# 03_MCU.net
KiCad netlist of a schematic drawn in Altium Designer
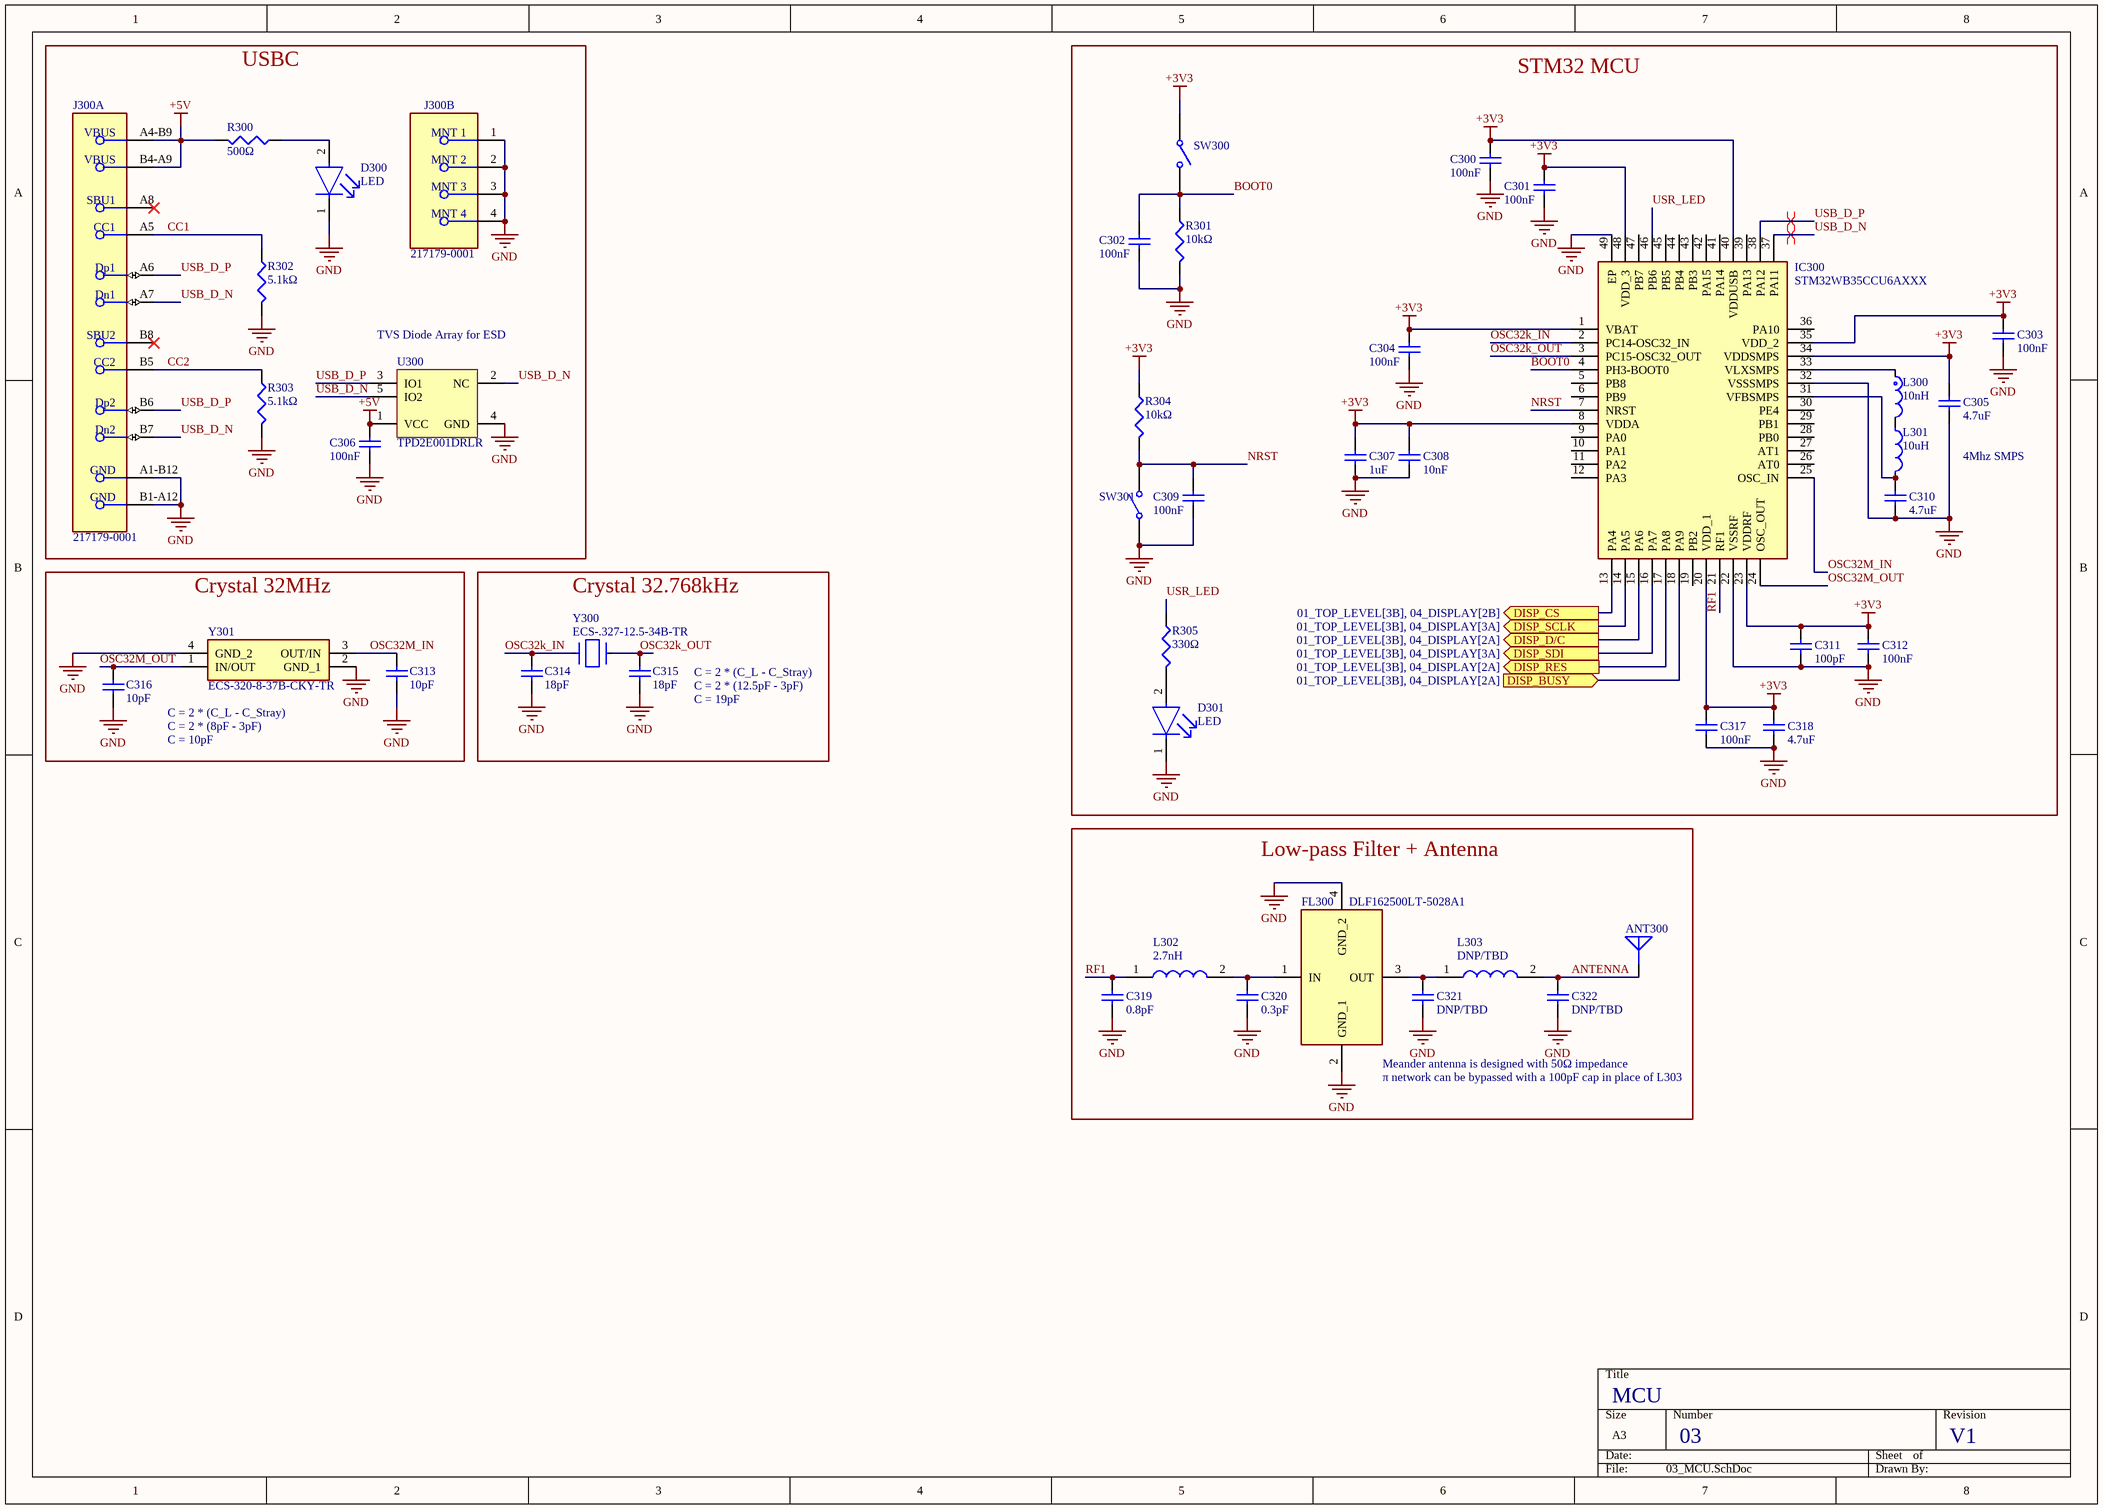
[diagram p0: 03_MCU.SchDoc]

(export (version "E")
  (design (tool "Eeschema 10.0.6"))
  (components
    (comp (ref "ANT300")
      (value "MEANDER_ANTENNA")
      (footprint "MEANDER_ANTENNA")
      (description "2.4GHz meander antenna")
      (libsource (lib "Schlib1") (part "MEANDER_ANTENNA"))
    )
    (comp (ref "C300")
      (value "100nF")
      (footprint "CAPC1005X55X25LL05T10")
      (description "Chip Capacitor, 1 uF, +/- 10%, 6.3 V, 0402 (1005 Metric)")
      (fields (field (name "TOLERANCE") "10%") (field (name "Comment") "Capacitor 1 uF +/- 10% 6.3 V 0402"))
      (libsource (lib "CPRT Workspace") (part "CAP-NP-2"))
    )
    (comp (ref "C301")
      (value "100nF")
      (footprint "CAPC1005X55X25LL05T10")
      (description "Chip Capacitor, 1 uF, +/- 10%, 6.3 V, 0402 (1005 Metric)")
      (fields (field (name "TOLERANCE") "10%") (field (name "Comment") "Capacitor 1 uF +/- 10% 6.3 V 0402"))
      (libsource (lib "CPRT Workspace") (part "CAP-NP-2"))
    )
    (comp (ref "C302")
      (value "100nF")
      (footprint "CAPC1005X55X25LL05T10")
      (description "Chip Capacitor, 1 uF, +/- 10%, 6.3 V, 0402 (1005 Metric)")
      (fields (field (name "TOLERANCE") "10%") (field (name "Comment") "Capacitor 1 uF +/- 10% 6.3 V 0402"))
      (libsource (lib "CPRT Workspace") (part "CAP-NP-2"))
    )
    (comp (ref "C303")
      (value "100nF")
      (footprint "CAPC1005X55X25LL05T10")
      (description "Chip Capacitor, 1 uF, +/- 10%, 6.3 V, 0402 (1005 Metric)")
      (fields (field (name "TOLERANCE") "10%") (field (name "Comment") "Capacitor 1 uF +/- 10% 6.3 V 0402"))
      (libsource (lib "CPRT Workspace") (part "CAP-NP-2"))
    )
    (comp (ref "C304")
      (value "100nF")
      (footprint "CAPC1005X55X25LL05T10")
      (description "Chip Capacitor, 1 uF, +/- 10%, 6.3 V, 0402 (1005 Metric)")
      (fields (field (name "TOLERANCE") "10%") (field (name "Comment") "Capacitor 1 uF +/- 10% 6.3 V 0402"))
      (libsource (lib "CPRT Workspace") (part "CAP-NP-2"))
    )
    (comp (ref "C305")
      (value "4.7uF")
      (footprint "CAPC1005X55X25LL05T10")
      (description "Chip Capacitor, 1 uF, +/- 10%, 6.3 V, 0402 (1005 Metric)")
      (fields (field (name "TOLERANCE") "10%") (field (name "Comment") "Capacitor 1 uF +/- 10% 6.3 V 0402"))
      (libsource (lib "CPRT Workspace") (part "CAP-NP-2"))
    )
    (comp (ref "C306")
      (value "100nF")
      (footprint "CAPC1005X55X25LL05T10")
      (description "Chip Capacitor, 1 uF, +/- 10%, 6.3 V, 0402 (1005 Metric)")
      (fields (field (name "TOLERANCE") "10%") (field (name "Comment") "Capacitor 1 uF +/- 10% 6.3 V 0402"))
      (libsource (lib "CPRT Workspace") (part "CAP-NP-2"))
    )
    (comp (ref "C307")
      (value "1uF")
      (footprint "CAPC1005X55X25LL05T10")
      (description "Chip Capacitor, 1 uF, +/- 10%, 6.3 V, 0402 (1005 Metric)")
      (fields (field (name "TOLERANCE") "10%") (field (name "Comment") "Capacitor 1 uF +/- 10% 6.3 V 0402"))
      (libsource (lib "CPRT Workspace") (part "CAP-NP-2"))
    )
    (comp (ref "C308")
      (value "10nF")
      (footprint "CAPC1005X55X25LL05T10")
      (description "Chip Capacitor, 1 uF, +/- 10%, 6.3 V, 0402 (1005 Metric)")
      (fields (field (name "TOLERANCE") "10%") (field (name "Comment") "Capacitor 1 uF +/- 10% 6.3 V 0402"))
      (libsource (lib "CPRT Workspace") (part "CAP-NP-2"))
    )
    (comp (ref "C309")
      (value "100nF")
      (footprint "CAPC1005X55X25LL05T10")
      (description "Chip Capacitor, 1 uF, +/- 10%, 6.3 V, 0402 (1005 Metric)")
      (fields (field (name "TOLERANCE") "10%") (field (name "Comment") "Capacitor 1 uF +/- 10% 6.3 V 0402"))
      (libsource (lib "CPRT Workspace") (part "CAP-NP-2"))
    )
    (comp (ref "C310")
      (value "4.7uF")
      (footprint "CAPC1005X55X25LL05T10")
      (description "Chip Capacitor, 1 uF, +/- 10%, 6.3 V, 0402 (1005 Metric)")
      (fields (field (name "TOLERANCE") "10%") (field (name "Comment") "Capacitor 1 uF +/- 10% 6.3 V 0402"))
      (libsource (lib "CPRT Workspace") (part "CAP-NP-2"))
    )
    (comp (ref "C311")
      (value "100pF")
      (footprint "CAPC1005X55X25LL05T10")
      (description "Chip Capacitor, 1 uF, +/- 10%, 6.3 V, 0402 (1005 Metric)")
      (fields (field (name "TOLERANCE") "10%") (field (name "Comment") "Capacitor 1 uF +/- 10% 6.3 V 0402"))
      (libsource (lib "CPRT Workspace") (part "CAP-NP-2"))
    )
    (comp (ref "C312")
      (value "100nF")
      (footprint "CAPC1005X55X25LL05T10")
      (description "Chip Capacitor, 1 uF, +/- 10%, 6.3 V, 0402 (1005 Metric)")
      (fields (field (name "TOLERANCE") "10%") (field (name "Comment") "Capacitor 1 uF +/- 10% 6.3 V 0402"))
      (libsource (lib "CPRT Workspace") (part "CAP-NP-2"))
    )
    (comp (ref "C313")
      (value "10pF")
      (footprint "CAPC1005X55X25LL05T10")
      (description "Chip Capacitor, 1 uF, +/- 10%, 6.3 V, 0402 (1005 Metric)")
      (fields (field (name "TOLERANCE") "10%") (field (name "Comment") "Capacitor 1 uF +/- 10% 6.3 V 0402"))
      (libsource (lib "CPRT Workspace") (part "CAP-NP-2"))
    )
    (comp (ref "C314")
      (value "18pF")
      (footprint "CAPC1005X55X25LL05T10")
      (description "Chip Capacitor, 1 uF, +/- 10%, 6.3 V, 0402 (1005 Metric)")
      (fields (field (name "TOLERANCE") "10%") (field (name "Comment") "Capacitor 1 uF +/- 10% 6.3 V 0402"))
      (libsource (lib "CPRT Workspace") (part "CAP-NP-2"))
    )
    (comp (ref "C315")
      (value "18pF")
      (footprint "CAPC1005X55X25LL05T10")
      (description "Chip Capacitor, 1 uF, +/- 10%, 6.3 V, 0402 (1005 Metric)")
      (fields (field (name "TOLERANCE") "10%") (field (name "Comment") "Capacitor 1 uF +/- 10% 6.3 V 0402"))
      (libsource (lib "CPRT Workspace") (part "CAP-NP-2"))
    )
    (comp (ref "C316")
      (value "10pF")
      (footprint "CAPC1005X55X25LL05T10")
      (description "Chip Capacitor, 1 uF, +/- 10%, 6.3 V, 0402 (1005 Metric)")
      (fields (field (name "TOLERANCE") "10%") (field (name "Comment") "Capacitor 1 uF +/- 10% 6.3 V 0402"))
      (libsource (lib "CPRT Workspace") (part "CAP-NP-2"))
    )
    (comp (ref "C317")
      (value "100nF")
      (footprint "CAPC1005X55X25LL05T10")
      (description "Chip Capacitor, 1 uF, +/- 10%, 6.3 V, 0402 (1005 Metric)")
      (fields (field (name "TOLERANCE") "10%") (field (name "Comment") "Capacitor 1 uF +/- 10% 6.3 V 0402"))
      (libsource (lib "CPRT Workspace") (part "CAP-NP-2"))
    )
    (comp (ref "C318")
      (value "4.7uF")
      (footprint "CAPC1005X55X25LL05T10")
      (description "Chip Capacitor, 1 uF, +/- 10%, 6.3 V, 0402 (1005 Metric)")
      (fields (field (name "TOLERANCE") "10%") (field (name "Comment") "Capacitor 1 uF +/- 10% 6.3 V 0402"))
      (libsource (lib "CPRT Workspace") (part "CAP-NP-2"))
    )
    (comp (ref "C319")
      (value "0.8pF")
      (footprint "CAPC1005X55X25LL05T10")
      (description "Chip Capacitor, 1 uF, +/- 10%, 6.3 V, 0402 (1005 Metric)")
      (fields (field (name "TOLERANCE") "10%") (field (name "Comment") "Capacitor 1 uF +/- 10% 6.3 V 0402"))
      (libsource (lib "CPRT Workspace") (part "CAP-NP-2"))
    )
    (comp (ref "C320")
      (value "0.3pF")
      (footprint "CAPC1005X55X25LL05T10")
      (description "Chip Capacitor, 1 uF, +/- 10%, 6.3 V, 0402 (1005 Metric)")
      (fields (field (name "TOLERANCE") "10%") (field (name "Comment") "Capacitor 1 uF +/- 10% 6.3 V 0402"))
      (libsource (lib "CPRT Workspace") (part "CAP-NP-2"))
    )
    (comp (ref "C321")
      (value "DNP/TBD")
      (footprint "CAPC1005X55X25LL05T10")
      (description "Chip Capacitor, 1 uF, +/- 10%, 6.3 V, 0402 (1005 Metric)")
      (fields (field (name "TOLERANCE") "10%") (field (name "Comment") "Capacitor 1 uF +/- 10% 6.3 V 0402"))
      (libsource (lib "CPRT Workspace") (part "CAP-NP-2"))
    )
    (comp (ref "C322")
      (value "DNP/TBD")
      (footprint "CAPC1005X55X25LL05T10")
      (description "Chip Capacitor, 1 uF, +/- 10%, 6.3 V, 0402 (1005 Metric)")
      (fields (field (name "TOLERANCE") "10%") (field (name "Comment") "Capacitor 1 uF +/- 10% 6.3 V 0402"))
      (libsource (lib "CPRT Workspace") (part "CAP-NP-2"))
    )
    (comp (ref "D300")
      (value "LED")
      (footprint "FP-VLMO1500-GS08-MFG")
      (description "VLMO1500-GS08 LED Uni-Color Soft Orange 611nm 2-Pin Chip 0402(1006Metric) T/R")
      (libsource (lib "Altium Content Vault") (part "75a0115997dd6a71327e26aab64f6f8"))
    )
    (comp (ref "D301")
      (value "LED")
      (footprint "FP-VLMO1500-GS08-MFG")
      (description "VLMO1500-GS08 LED Uni-Color Soft Orange 611nm 2-Pin Chip 0402(1006Metric) T/R")
      (libsource (lib "Altium Content Vault") (part "75a0115997dd6a71327e26aab64f6f8"))
    )
    (comp (ref "FL300")
      (value "DLF162500LT-5028A1")
      (footprint "DLF162500LT5028A1")
      (description "Filter")
      (fields (field (name "MOUSER PART NUMBER") "810-DLF16250LT5028A1"))
      (libsource (lib "Schlib1") (part "DLF162500LT-5028A1"))
    )
    (comp (ref "IC300")
      (value "STM32WB35CCU6AXXX")
      (footprint "QFN50P700X700X65-49N-D")
      (description "Integrated Circuit")
      (libsource (lib "Schlib1") (part "STM32WB35CCU6AXXX"))
    )
    (comp (ref "J300")
      (value "217179-0001")
      (footprint "FP-2171790001-MFG")
      (description "CONN RCP USB2.0 TYP C 24P SMD RA")
      (libsource (lib "Altium Content Vault") (part "8b86497a633d14b3f74642136fc0ce6"))
    )
    (comp (ref "L300")
      (value "10nH")
      (footprint "FP-LQG15WH_02-MFG")
      (description "Multilayer type Inductor for Automotive 10nH ±5% 0.19Ω 500mA 0402")
      (fields (field (name "TOLERANCE") "5%"))
      (libsource (lib "Altium Content Vault") (part "4cc4b267dca4c8e51f7102f422741d8"))
    )
    (comp (ref "L301")
      (value "10uH")
      (footprint "FP-LQM21FN_70-MFG")
      (description "FIXED IND 10UH 100MA 780MOHM SMD")
      (fields (field (name "TOLERANCE") "20%"))
      (libsource (lib "Altium Content Vault") (part "725321dda6339637d4d059423bc1c3c"))
    )
    (comp (ref "L302")
      (value "2.7nH")
      (footprint "LQG15WH0N7B02D")
      (description "Inductor")
      (fields
        (field (name "MANUFACTURER_PART_NUMBER") "LQG15HS2N7S02D")
        (field (name "MOUSER PART NUMBER") "81-LQG15HS2N7S02D")
      )
      (libsource (lib "Schlib1") (part "LQG15HS2N7S02D"))
    )
    (comp (ref "L303")
      (value "DNP/TBD")
      (footprint "LQG15WH0N7B02D")
      (description "Inductor")
      (fields
        (field (name "MANUFACTURER_PART_NUMBER") "LQG15HS2N7S02D")
        (field (name "MOUSER PART NUMBER") "81-LQG15HS2N7S02D")
      )
      (libsource (lib "Schlib1") (part "LQG15HS2N7S02D"))
    )
    (comp (ref "R300")
      (value "500Ω")
      (footprint "RESC0402(1005)_L")
      (description "100R 0.063W 1% 0402 (1005 Metric)  SMD")
      (fields (field (name "TOLERANCE") "1%") (field (name "POWER") "63mW"))
      (libsource (lib "CPRT Workspace") (part "100R2F"))
    )
    (comp (ref "R301")
      (value "10kΩ")
      (footprint "RESC0402(1005)_L")
      (description "100R 0.063W 1% 0402 (1005 Metric)  SMD")
      (fields (field (name "TOLERANCE") "1%") (field (name "POWER") "63mW"))
      (libsource (lib "CPRT Workspace") (part "100R2F"))
    )
    (comp (ref "R302")
      (value "5.1kΩ")
      (footprint "RESC0402(1005)_L")
      (description "100R 0.063W 1% 0402 (1005 Metric)  SMD")
      (fields (field (name "TOLERANCE") "1%") (field (name "POWER") "63mW"))
      (libsource (lib "CPRT Workspace") (part "100R2F"))
    )
    (comp (ref "R303")
      (value "5.1kΩ")
      (footprint "RESC0402(1005)_L")
      (description "100R 0.063W 1% 0402 (1005 Metric)  SMD")
      (fields (field (name "TOLERANCE") "1%") (field (name "POWER") "63mW"))
      (libsource (lib "CPRT Workspace") (part "100R2F"))
    )
    (comp (ref "R304")
      (value "10kΩ")
      (footprint "RESC0402(1005)_L")
      (description "100R 0.063W 1% 0402 (1005 Metric)  SMD")
      (fields (field (name "TOLERANCE") "1%") (field (name "POWER") "63mW"))
      (libsource (lib "CPRT Workspace") (part "100R2F"))
    )
    (comp (ref "R305")
      (value "330Ω")
      (footprint "RESC0402(1005)_L")
      (description "100R 0.063W 1% 0402 (1005 Metric)  SMD")
      (fields (field (name "TOLERANCE") "1%") (field (name "POWER") "63mW"))
      (libsource (lib "CPRT Workspace") (part "100R2F"))
    )
    (comp (ref "SW300")
      (value "434111050826")
      (footprint "434111050826")
      (description "Switch Tactile Spst-no 0.05A 12V")
      (libsource (lib "Altium Content Vault") (part "SPST-NO_2P"))
    )
    (comp (ref "SW301")
      (value "434111050826")
      (footprint "434111050826")
      (description "Switch Tactile Spst-no 0.05A 12V")
      (libsource (lib "Altium Content Vault") (part "SPST-NO_2P"))
    )
    (comp (ref "U300")
      (value "TPD2E001DRLR")
      (footprint "DRL0005A_L")
      (fields (field (name "MANUFACTURER") "Texas Instruments"))
      (libsource (lib "Altium Content Vault") (part "TI-TPD2E001-SOT_DRL-5"))
    )
    (comp (ref "Y300")
      (value "ECS-.327-12.5-34B-TR")
      (footprint "FP-ECX-31B-MFG")
      (description "CRYSTAL 32.7680KHZ 12.5PF SMD")
      (libsource (lib "Altium Content Vault") (part "99724985039315a44fd0d1401b84e49"))
    )
    (comp (ref "Y301")
      (value "ECS-320-8-37B-CKY-TR")
      (footprint "ECS320837BCKYTR")
      (description "Crystal or Oscillator")
      (fields (field (name "MOUSER PART NUMBER") "520-320-8-37B-CKYT"))
      (libsource (lib "Schlib1") (part "ECS-320-8-37B-CKY-TR"))
    )
  )
  (nets
    (net (code "1") (name "+3V3") (class "Default")
      (node (ref "C300") (pin "2") (pinfunction "2_2") (pintype "passive"))
      (node (ref "C301") (pin "2") (pinfunction "2_2") (pintype "passive"))
      (node (ref "C303") (pin "2") (pinfunction "2_2") (pintype "passive"))
      (node (ref "C304") (pin "2") (pinfunction "2_2") (pintype "passive"))
      (node (ref "C305") (pin "2") (pinfunction "2_2") (pintype "passive"))
      (node (ref "C307") (pin "2") (pinfunction "2_2") (pintype "passive"))
      (node (ref "C308") (pin "2") (pinfunction "2_2") (pintype "passive"))
      (node (ref "C311") (pin "2") (pinfunction "2_2") (pintype "passive"))
      (node (ref "C312") (pin "2") (pinfunction "2_2") (pintype "passive"))
      (node (ref "C317") (pin "2") (pinfunction "2_2") (pintype "passive"))
      (node (ref "C318") (pin "2") (pinfunction "2_2") (pintype "passive"))
      (node (ref "IC300") (pin "1") (pinfunction "VBAT_1") (pintype "passive"))
      (node (ref "IC300") (pin "20") (pinfunction "VDD_1_20") (pintype "passive"))
      (node (ref "IC300") (pin "23") (pinfunction "VDDRF_23") (pintype "passive"))
      (node (ref "IC300") (pin "34") (pinfunction "VDDSMPS_34") (pintype "passive"))
      (node (ref "IC300") (pin "35") (pinfunction "VDD_2_35") (pintype "passive"))
      (node (ref "IC300") (pin "40") (pinfunction "VDDUSB_40") (pintype "passive"))
      (node (ref "IC300") (pin "48") (pinfunction "VDD_3_48") (pintype "passive"))
      (node (ref "IC300") (pin "8") (pinfunction "VDDA_8") (pintype "passive"))
      (node (ref "R304") (pin "1") (pinfunction "1_1") (pintype "passive"))
      (node (ref "SW300") (pin "1") (pinfunction "1_1") (pintype "passive"))
    )
    (net (code "2") (name "+5V") (class "Default")
      (node (ref "C306") (pin "2") (pinfunction "2_2") (pintype "passive"))
      (node (ref "J300") (pin "A4-B9") (pinfunction "VBUS_A4-B9") (pintype "power_in"))
      (node (ref "J300") (pin "B4-A9") (pinfunction "VBUS_B4-A9") (pintype "power_in"))
      (node (ref "R300") (pin "2") (pinfunction "2_2") (pintype "passive"))
      (node (ref "U300") (pin "1") (pinfunction "VCC_1") (pintype "power_in"))
    )
    (net (code "3") (name "/ANTENNA") (class "Default")
      (node (ref "ANT300") (pin "0") (pinfunction "0_0") (pintype "passive"))
      (node (ref "C322") (pin "2") (pinfunction "2_2") (pintype "passive"))
      (node (ref "L303") (pin "2") (pinfunction "2_2") (pintype "passive"))
    )
    (net (code "4") (name "/BOOT0") (class "Default")
      (node (ref "C302") (pin "2") (pinfunction "2_2") (pintype "passive"))
      (node (ref "IC300") (pin "4") (pinfunction "PH3-BOOT0_4") (pintype "passive"))
      (node (ref "R301") (pin "1") (pinfunction "1_1") (pintype "passive"))
      (node (ref "SW300") (pin "2") (pinfunction "2_2") (pintype "passive"))
    )
    (net (code "5") (name "/CC1") (class "Default")
      (node (ref "J300") (pin "A5") (pinfunction "CC1_A5") (pintype "passive"))
      (node (ref "R302") (pin "1") (pinfunction "1_1") (pintype "passive"))
    )
    (net (code "6") (name "/CC2") (class "Default")
      (node (ref "J300") (pin "B5") (pinfunction "CC2_B5") (pintype "passive"))
      (node (ref "R303") (pin "1") (pinfunction "1_1") (pintype "passive"))
    )
    (net (code "7") (name "/DISP_BUSY") (class "Default")
      (node (ref "IC300") (pin "18") (pinfunction "PA9_18") (pintype "passive"))
    )
    (net (code "8") (name "/DISP_CS") (class "Default")
      (node (ref "IC300") (pin "13") (pinfunction "PA4_13") (pintype "passive"))
    )
    (net (code "9") (name "/DISP_D{slash}C") (class "Default")
      (node (ref "IC300") (pin "15") (pinfunction "PA6_15") (pintype "passive"))
    )
    (net (code "10") (name "/DISP_RES") (class "Default")
      (node (ref "IC300") (pin "17") (pinfunction "PA8_17") (pintype "passive"))
    )
    (net (code "11") (name "/DISP_SCLK") (class "Default")
      (node (ref "IC300") (pin "14") (pinfunction "PA5_14") (pintype "passive"))
    )
    (net (code "12") (name "/DISP_SDI") (class "Default")
      (node (ref "IC300") (pin "16") (pinfunction "PA7_16") (pintype "passive"))
    )
    (net (code "13") (name "/NRST") (class "Default")
      (node (ref "C309") (pin "2") (pinfunction "2_2") (pintype "passive"))
      (node (ref "IC300") (pin "7") (pinfunction "NRST_7") (pintype "passive"))
      (node (ref "R304") (pin "2") (pinfunction "2_2") (pintype "passive"))
      (node (ref "SW301") (pin "2") (pinfunction "2_2") (pintype "passive"))
    )
    (net (code "14") (name "/OSC32M_IN") (class "Default")
      (node (ref "C313") (pin "2") (pinfunction "2_2") (pintype "passive"))
      (node (ref "IC300") (pin "25") (pinfunction "OSC_IN_25") (pintype "passive"))
      (node (ref "Y301") (pin "3") (pinfunction "OUT/IN_3") (pintype "passive"))
    )
    (net (code "15") (name "/OSC32M_OUT") (class "Default")
      (node (ref "C316") (pin "2") (pinfunction "2_2") (pintype "passive"))
      (node (ref "IC300") (pin "24") (pinfunction "OSC_OUT_24") (pintype "passive"))
      (node (ref "Y301") (pin "1") (pinfunction "IN/OUT_1") (pintype "passive"))
    )
    (net (code "16") (name "/OSC32k_IN") (class "Default")
      (node (ref "C314") (pin "2") (pinfunction "2_2") (pintype "passive"))
      (node (ref "IC300") (pin "2") (pinfunction "PC14-OSC32_IN_2") (pintype "passive"))
      (node (ref "Y300") (pin "1") (pinfunction "In/Out_1") (pintype "passive"))
    )
    (net (code "17") (name "/OSC32k_OUT") (class "Default")
      (node (ref "C315") (pin "2") (pinfunction "2_2") (pintype "passive"))
      (node (ref "IC300") (pin "3") (pinfunction "PC15-OSC32_OUT_3") (pintype "passive"))
      (node (ref "Y300") (pin "2") (pinfunction "Out/In_2") (pintype "passive"))
    )
    (net (code "18") (name "/RF1") (class "Default")
      (node (ref "C319") (pin "2") (pinfunction "2_2") (pintype "passive"))
      (node (ref "IC300") (pin "21") (pinfunction "RF1_21") (pintype "passive"))
      (node (ref "L302") (pin "1") (pinfunction "1_1") (pintype "passive"))
    )
    (net (code "19") (name "/USB_D_N") (class "Default")
      (node (ref "IC300") (pin "37") (pinfunction "PA11_37") (pintype "passive"))
      (node (ref "J300") (pin "A7") (pinfunction "Dn1_A7") (pintype "bidirectional"))
      (node (ref "J300") (pin "B7") (pinfunction "Dn2_B7") (pintype "bidirectional"))
      (node (ref "U300") (pin "2") (pinfunction "NC_2") (pintype "passive"))
      (node (ref "U300") (pin "5") (pinfunction "IO2_5") (pintype "passive"))
    )
    (net (code "20") (name "/USB_D_P") (class "Default")
      (node (ref "IC300") (pin "38") (pinfunction "PA12_38") (pintype "passive"))
      (node (ref "J300") (pin "A6") (pinfunction "Dp1_A6") (pintype "bidirectional"))
      (node (ref "J300") (pin "B6") (pinfunction "Dp2_B6") (pintype "bidirectional"))
      (node (ref "U300") (pin "3") (pinfunction "IO1_3") (pintype "passive"))
    )
    (net (code "21") (name "/USR_LED") (class "Default")
      (node (ref "IC300") (pin "46") (pinfunction "PB6_46") (pintype "passive"))
      (node (ref "R305") (pin "1") (pinfunction "1_1") (pintype "passive"))
    )
    (net (code "22") (name "GND") (class "Default")
      (node (ref "C300") (pin "1") (pinfunction "1_1") (pintype "passive"))
      (node (ref "C301") (pin "1") (pinfunction "1_1") (pintype "passive"))
      (node (ref "C302") (pin "1") (pinfunction "1_1") (pintype "passive"))
      (node (ref "C303") (pin "1") (pinfunction "1_1") (pintype "passive"))
      (node (ref "C304") (pin "1") (pinfunction "1_1") (pintype "passive"))
      (node (ref "C305") (pin "1") (pinfunction "1_1") (pintype "passive"))
      (node (ref "C306") (pin "1") (pinfunction "1_1") (pintype "passive"))
      (node (ref "C307") (pin "1") (pinfunction "1_1") (pintype "passive"))
      (node (ref "C308") (pin "1") (pinfunction "1_1") (pintype "passive"))
      (node (ref "C309") (pin "1") (pinfunction "1_1") (pintype "passive"))
      (node (ref "C310") (pin "1") (pinfunction "1_1") (pintype "passive"))
      (node (ref "C311") (pin "1") (pinfunction "1_1") (pintype "passive"))
      (node (ref "C312") (pin "1") (pinfunction "1_1") (pintype "passive"))
      (node (ref "C313") (pin "1") (pinfunction "1_1") (pintype "passive"))
      (node (ref "C314") (pin "1") (pinfunction "1_1") (pintype "passive"))
      (node (ref "C315") (pin "1") (pinfunction "1_1") (pintype "passive"))
      (node (ref "C316") (pin "1") (pinfunction "1_1") (pintype "passive"))
      (node (ref "C317") (pin "1") (pinfunction "1_1") (pintype "passive"))
      (node (ref "C318") (pin "1") (pinfunction "1_1") (pintype "passive"))
      (node (ref "C319") (pin "1") (pinfunction "1_1") (pintype "passive"))
      (node (ref "C320") (pin "1") (pinfunction "1_1") (pintype "passive"))
      (node (ref "C321") (pin "1") (pinfunction "1_1") (pintype "passive"))
      (node (ref "C322") (pin "1") (pinfunction "1_1") (pintype "passive"))
      (node (ref "D300") (pin "1") (pinfunction "C_1") (pintype "passive"))
      (node (ref "D301") (pin "1") (pinfunction "C_1") (pintype "passive"))
      (node (ref "FL300") (pin "2") (pinfunction "GND_1_2") (pintype "passive"))
      (node (ref "FL300") (pin "4") (pinfunction "GND_2_4") (pintype "passive"))
      (node (ref "IC300") (pin "22") (pinfunction "VSSRF_22") (pintype "passive"))
      (node (ref "IC300") (pin "32") (pinfunction "VSSSMPS_32") (pintype "passive"))
      (node (ref "IC300") (pin "49") (pinfunction "EP_49") (pintype "passive"))
      (node (ref "J300") (pin "1") (pinfunction "MNT_1_1") (pintype "passive"))
      (node (ref "J300") (pin "2") (pinfunction "MNT_2_2") (pintype "passive"))
      (node (ref "J300") (pin "3") (pinfunction "MNT_3_3") (pintype "power_in"))
      (node (ref "J300") (pin "4") (pinfunction "MNT_4_4") (pintype "power_in"))
      (node (ref "J300") (pin "A1-B12") (pinfunction "GND_A1-B12") (pintype "power_in"))
      (node (ref "J300") (pin "B1-A12") (pinfunction "GND_B1-A12") (pintype "power_in"))
      (node (ref "R301") (pin "2") (pinfunction "2_2") (pintype "passive"))
      (node (ref "R302") (pin "2") (pinfunction "2_2") (pintype "passive"))
      (node (ref "R303") (pin "2") (pinfunction "2_2") (pintype "passive"))
      (node (ref "SW301") (pin "1") (pinfunction "1_1") (pintype "passive"))
      (node (ref "U300") (pin "4") (pinfunction "GND_4") (pintype "power_in"))
      (node (ref "Y301") (pin "2") (pinfunction "GND_1_2") (pintype "passive"))
      (node (ref "Y301") (pin "4") (pinfunction "GND_2_4") (pintype "passive"))
    )
    (net (code "23") (name "Net-(D300-A)") (class "Default")
      (node (ref "D300") (pin "2") (pinfunction "A_2") (pintype "passive"))
      (node (ref "R300") (pin "1") (pinfunction "1_1") (pintype "passive"))
    )
    (net (code "24") (name "Net-(D301-A)") (class "Default")
      (node (ref "D301") (pin "2") (pinfunction "A_2") (pintype "passive"))
      (node (ref "R305") (pin "2") (pinfunction "2_2") (pintype "passive"))
    )
    (net (code "25") (name "Net-(FL300-IN)") (class "Default")
      (node (ref "C320") (pin "2") (pinfunction "2_2") (pintype "passive"))
      (node (ref "FL300") (pin "1") (pinfunction "IN_1") (pintype "passive"))
      (node (ref "L302") (pin "2") (pinfunction "2_2") (pintype "passive"))
    )
    (net (code "26") (name "Net-(FL300-OUT)") (class "Default")
      (node (ref "C321") (pin "2") (pinfunction "2_2") (pintype "passive"))
      (node (ref "FL300") (pin "3") (pinfunction "OUT_3") (pintype "passive"))
      (node (ref "L303") (pin "1") (pinfunction "1_1") (pintype "passive"))
    )
    (net (code "27") (name "Net-(IC300-VFBSMPS)") (class "Default")
      (node (ref "C310") (pin "2") (pinfunction "2_2") (pintype "passive"))
      (node (ref "IC300") (pin "31") (pinfunction "VFBSMPS_31") (pintype "passive"))
      (node (ref "L301") (pin "2") (pinfunction "2_2") (pintype "passive"))
    )
    (net (code "28") (name "Net-(IC300-VLXSMPS)") (class "Default")
      (node (ref "IC300") (pin "33") (pinfunction "VLXSMPS_33") (pintype "passive"))
      (node (ref "L300") (pin "1") (pinfunction "1_1") (pintype "passive"))
    )
    (net (code "29") (name "Net-(L300-Pad2)") (class "Default")
      (node (ref "L300") (pin "2") (pinfunction "2_2") (pintype "passive"))
      (node (ref "L301") (pin "1") (pinfunction "1_1") (pintype "passive"))
    )
    (net (code "30") (name "unconnected-(IC300-AT0-Pad26)") (class "Default")
      (node (ref "IC300") (pin "26") (pinfunction "AT0_26") (pintype "passive"))
    )
    (net (code "31") (name "unconnected-(IC300-AT1-Pad27)") (class "Default")
      (node (ref "IC300") (pin "27") (pinfunction "AT1_27") (pintype "passive"))
    )
    (net (code "32") (name "unconnected-(IC300-PA0-Pad9)") (class "Default")
      (node (ref "IC300") (pin "9") (pinfunction "PA0_9") (pintype "passive"))
    )
    (net (code "33") (name "unconnected-(IC300-PA1-Pad10)") (class "Default")
      (node (ref "IC300") (pin "10") (pinfunction "PA1_10") (pintype "passive"))
    )
    (net (code "34") (name "unconnected-(IC300-PA2-Pad11)") (class "Default")
      (node (ref "IC300") (pin "11") (pinfunction "PA2_11") (pintype "passive"))
    )
    (net (code "35") (name "unconnected-(IC300-PA3-Pad12)") (class "Default")
      (node (ref "IC300") (pin "12") (pinfunction "PA3_12") (pintype "passive"))
    )
    (net (code "36") (name "unconnected-(IC300-PA10-Pad36)") (class "Default")
      (node (ref "IC300") (pin "36") (pinfunction "PA10_36") (pintype "passive"))
    )
    (net (code "37") (name "unconnected-(IC300-PA13-Pad39)") (class "Default")
      (node (ref "IC300") (pin "39") (pinfunction "PA13_39") (pintype "passive"))
    )
    (net (code "38") (name "unconnected-(IC300-PA14-Pad41)") (class "Default")
      (node (ref "IC300") (pin "41") (pinfunction "PA14_41") (pintype "passive"))
    )
    (net (code "39") (name "unconnected-(IC300-PA15-Pad42)") (class "Default")
      (node (ref "IC300") (pin "42") (pinfunction "PA15_42") (pintype "passive"))
    )
    (net (code "40") (name "unconnected-(IC300-PB0-Pad28)") (class "Default")
      (node (ref "IC300") (pin "28") (pinfunction "PB0_28") (pintype "passive"))
    )
    (net (code "41") (name "unconnected-(IC300-PB1-Pad29)") (class "Default")
      (node (ref "IC300") (pin "29") (pinfunction "PB1_29") (pintype "passive"))
    )
    (net (code "42") (name "unconnected-(IC300-PB2-Pad19)") (class "Default")
      (node (ref "IC300") (pin "19") (pinfunction "PB2_19") (pintype "passive"))
    )
    (net (code "43") (name "unconnected-(IC300-PB3-Pad43)") (class "Default")
      (node (ref "IC300") (pin "43") (pinfunction "PB3_43") (pintype "passive"))
    )
    (net (code "44") (name "unconnected-(IC300-PB4-Pad44)") (class "Default")
      (node (ref "IC300") (pin "44") (pinfunction "PB4_44") (pintype "passive"))
    )
    (net (code "45") (name "unconnected-(IC300-PB5-Pad45)") (class "Default")
      (node (ref "IC300") (pin "45") (pinfunction "PB5_45") (pintype "passive"))
    )
    (net (code "46") (name "unconnected-(IC300-PB7-Pad47)") (class "Default")
      (node (ref "IC300") (pin "47") (pinfunction "PB7_47") (pintype "passive"))
    )
    (net (code "47") (name "unconnected-(IC300-PB8-Pad5)") (class "Default")
      (node (ref "IC300") (pin "5") (pinfunction "PB8_5") (pintype "passive"))
    )
    (net (code "48") (name "unconnected-(IC300-PB9-Pad6)") (class "Default")
      (node (ref "IC300") (pin "6") (pinfunction "PB9_6") (pintype "passive"))
    )
    (net (code "49") (name "unconnected-(IC300-PE4-Pad30)") (class "Default")
      (node (ref "IC300") (pin "30") (pinfunction "PE4_30") (pintype "passive"))
    )
    (net (code "50") (name "unconnected-(J300A-SBU1-PadA8)") (class "Default")
      (node (ref "J300") (pin "A8") (pinfunction "SBU1_A8") (pintype "passive+no_connect"))
    )
    (net (code "51") (name "unconnected-(J300A-SBU2-PadB8)") (class "Default")
      (node (ref "J300") (pin "B8") (pinfunction "SBU2_B8") (pintype "passive+no_connect"))
    )
  )
)
